# LED.net
KiCad netlist of a schematic drawn in Altium Designer
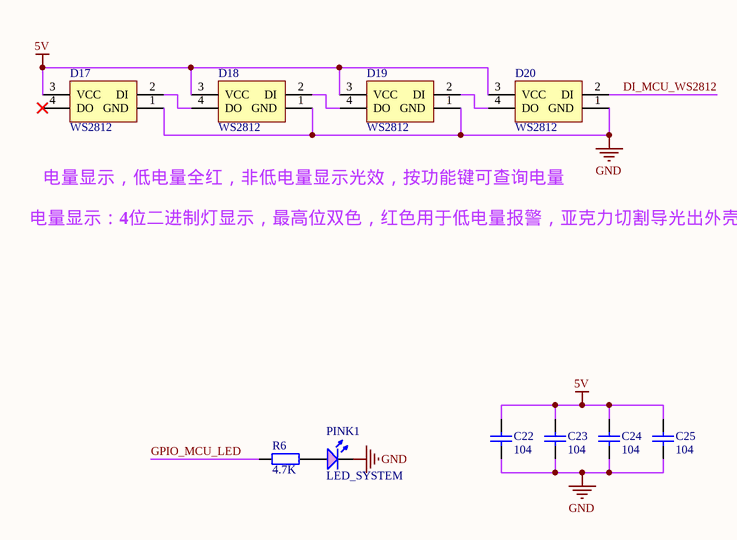
[diagram p0: LED.SchDoc]

(export (version "E")
  (design (tool "Eeschema 10.0.6"))
  (components
    (comp (ref "C22")
      (value "104")
      (footprint "Cap-0603")
      (description "贴片陶瓷电容")
      (libsource (lib "Miscellaneous Base") (part "CAP"))
    )
    (comp (ref "C23")
      (value "104")
      (footprint "Cap-0603")
      (description "贴片陶瓷电容")
      (libsource (lib "Miscellaneous Base") (part "CAP"))
    )
    (comp (ref "C24")
      (value "104")
      (footprint "Cap-0603")
      (description "贴片陶瓷电容")
      (libsource (lib "Miscellaneous Base") (part "CAP"))
    )
    (comp (ref "C25")
      (value "104")
      (footprint "Cap-0603")
      (description "贴片陶瓷电容")
      (libsource (lib "Miscellaneous Base") (part "CAP"))
    )
    (comp (ref "D17")
      (value "WS2812")
      (footprint "RGB_LED_1206")
      (fields (field (name "PUBLISHER") "mazhongwei"))
      (libsource (lib "Miscellaneous IC") (part "WS2812"))
    )
    (comp (ref "D18")
      (value "WS2812")
      (footprint "RGB_LED_1206")
      (fields (field (name "PUBLISHER") "mazhongwei"))
      (libsource (lib "Miscellaneous IC") (part "WS2812"))
    )
    (comp (ref "D19")
      (value "WS2812")
      (footprint "RGB_LED_1206")
      (fields (field (name "PUBLISHER") "mazhongwei"))
      (libsource (lib "Miscellaneous IC") (part "WS2812"))
    )
    (comp (ref "D20")
      (value "WS2812")
      (footprint "RGB_LED_1206")
      (fields (field (name "PUBLISHER") "mazhongwei"))
      (libsource (lib "Miscellaneous IC") (part "WS2812"))
    )
    (comp (ref "PINK1")
      (value "LED_SYSTEM")
      (footprint "LED_0603_R")
      (description "发光二极管")
      (libsource (lib "Miscellaneous Transistor") (part "LED_SMD_PINK"))
    )
    (comp (ref "R6")
      (value "4.7K")
      (footprint "Res-0603")
      (description "贴片电阻")
      (libsource (lib "Miscellaneous Base") (part "RES"))
    )
  )
  (nets
    (net (code "1") (name "/DI_MCU_WS2812") (class "Default")
      (node (ref "D20") (pin "2") (pinfunction "DI_2") (pintype "passive"))
    )
    (net (code "2") (name "/GPIO_MCU_LED") (class "Default")
      (node (ref "R6") (pin "2") (pinfunction "2_2") (pintype "passive"))
    )
    (net (code "3") (name "5V") (class "Default")
      (node (ref "C22") (pin "2") (pinfunction "2_2") (pintype "passive"))
      (node (ref "C23") (pin "2") (pinfunction "2_2") (pintype "passive"))
      (node (ref "C24") (pin "2") (pinfunction "2_2") (pintype "passive"))
      (node (ref "C25") (pin "2") (pinfunction "2_2") (pintype "passive"))
      (node (ref "D17") (pin "3") (pinfunction "VCC_3") (pintype "passive"))
      (node (ref "D18") (pin "3") (pinfunction "VCC_3") (pintype "passive"))
      (node (ref "D19") (pin "3") (pinfunction "VCC_3") (pintype "passive"))
      (node (ref "D20") (pin "3") (pinfunction "VCC_3") (pintype "passive"))
    )
    (net (code "4") (name "GND") (class "Default")
      (node (ref "C22") (pin "1") (pinfunction "1_1") (pintype "passive"))
      (node (ref "C23") (pin "1") (pinfunction "1_1") (pintype "passive"))
      (node (ref "C24") (pin "1") (pinfunction "1_1") (pintype "passive"))
      (node (ref "C25") (pin "1") (pinfunction "1_1") (pintype "passive"))
      (node (ref "D17") (pin "1") (pinfunction "GND_1") (pintype "passive"))
      (node (ref "D18") (pin "1") (pinfunction "GND_1") (pintype "passive"))
      (node (ref "D19") (pin "1") (pinfunction "GND_1") (pintype "passive"))
      (node (ref "D20") (pin "1") (pinfunction "GND_1") (pintype "passive"))
      (node (ref "PINK1") (pin "2") (pinfunction "K_2") (pintype "passive"))
    )
    (net (code "5") (name "Net-(D17-DI)") (class "Default")
      (node (ref "D17") (pin "2") (pinfunction "DI_2") (pintype "passive"))
      (node (ref "D18") (pin "4") (pinfunction "DO_4") (pintype "passive"))
    )
    (net (code "6") (name "Net-(D18-DI)") (class "Default")
      (node (ref "D18") (pin "2") (pinfunction "DI_2") (pintype "passive"))
      (node (ref "D19") (pin "4") (pinfunction "DO_4") (pintype "passive"))
    )
    (net (code "7") (name "Net-(D19-DI)") (class "Default")
      (node (ref "D19") (pin "2") (pinfunction "DI_2") (pintype "passive"))
      (node (ref "D20") (pin "4") (pinfunction "DO_4") (pintype "passive"))
    )
    (net (code "8") (name "Net-(PINK1-A)") (class "Default")
      (node (ref "PINK1") (pin "1") (pinfunction "A_1") (pintype "passive"))
      (node (ref "R6") (pin "1") (pinfunction "1_1") (pintype "passive"))
    )
    (net (code "9") (name "unconnected-(D17-DO-Pad4)") (class "Default")
      (node (ref "D17") (pin "4") (pinfunction "DO_4") (pintype "passive+no_connect"))
    )
  )
)
